# Dreamcast.net
KiCad netlist of a schematic drawn in EAGLE
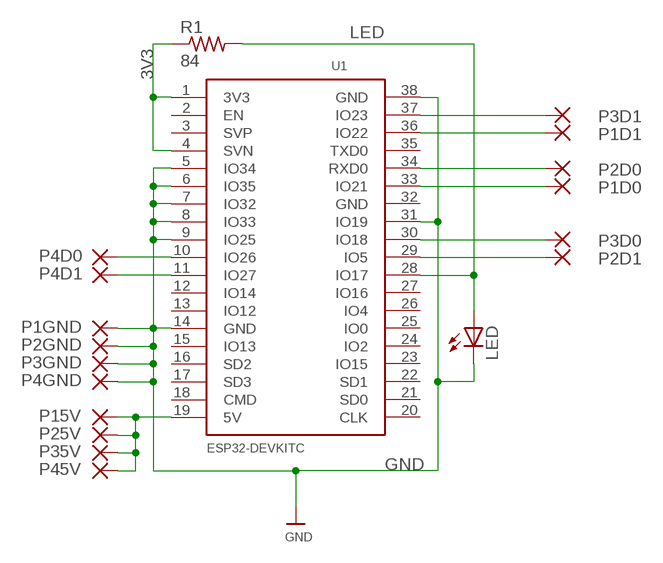
[diagram p0: schematic, sheet 1]

(export (version "E")
  (design (tool "Eeschema 10.0.6"))
  (components
    (comp (ref "LED")
      (value "LEDCHIPLED_1206")
      (footprint "eagle-import:CHIPLED_1206")
      (libsource (lib "eagle-import") (part "LEDCHIPLED_1206"))
    )
    (comp (ref "P1D0")
      (value "SMD5")
      (footprint "eagle-import:SMD2,54-5,08")
      (libsource (lib "eagle-import") (part "SMD5"))
    )
    (comp (ref "P1D1")
      (value "SMD5")
      (footprint "eagle-import:SMD2,54-5,08")
      (libsource (lib "eagle-import") (part "SMD5"))
    )
    (comp (ref "P1GND")
      (value "SMD5")
      (footprint "eagle-import:SMD2,54-5,08")
      (libsource (lib "eagle-import") (part "SMD5"))
    )
    (comp (ref "P2D0")
      (value "SMD5")
      (footprint "eagle-import:SMD2,54-5,08")
      (libsource (lib "eagle-import") (part "SMD5"))
    )
    (comp (ref "P2D1")
      (value "SMD5")
      (footprint "eagle-import:SMD2,54-5,08")
      (libsource (lib "eagle-import") (part "SMD5"))
    )
    (comp (ref "P2GND")
      (value "SMD5")
      (footprint "eagle-import:SMD2,54-5,08")
      (libsource (lib "eagle-import") (part "SMD5"))
    )
    (comp (ref "P3D0")
      (value "SMD5")
      (footprint "eagle-import:SMD2,54-5,08")
      (libsource (lib "eagle-import") (part "SMD5"))
    )
    (comp (ref "P3D1")
      (value "SMD5")
      (footprint "eagle-import:SMD2,54-5,08")
      (libsource (lib "eagle-import") (part "SMD5"))
    )
    (comp (ref "P3GND")
      (value "SMD5")
      (footprint "eagle-import:SMD2,54-5,08")
      (libsource (lib "eagle-import") (part "SMD5"))
    )
    (comp (ref "P4D0")
      (value "SMD5")
      (footprint "eagle-import:SMD2,54-5,08")
      (libsource (lib "eagle-import") (part "SMD5"))
    )
    (comp (ref "P4D1")
      (value "SMD5")
      (footprint "eagle-import:SMD2,54-5,08")
      (libsource (lib "eagle-import") (part "SMD5"))
    )
    (comp (ref "P4GND")
      (value "SMD5")
      (footprint "eagle-import:SMD2,54-5,08")
      (libsource (lib "eagle-import") (part "SMD5"))
    )
    (comp (ref "P15V")
      (value "SMD5")
      (footprint "eagle-import:SMD2,54-5,08")
      (libsource (lib "eagle-import") (part "SMD5"))
    )
    (comp (ref "P25V")
      (value "SMD5")
      (footprint "eagle-import:SMD2,54-5,08")
      (libsource (lib "eagle-import") (part "SMD5"))
    )
    (comp (ref "P35V")
      (value "SMD5")
      (footprint "eagle-import:SMD2,54-5,08")
      (libsource (lib "eagle-import") (part "SMD5"))
    )
    (comp (ref "P45V")
      (value "SMD5")
      (footprint "eagle-import:SMD2,54-5,08")
      (libsource (lib "eagle-import") (part "SMD5"))
    )
    (comp (ref "R1")
      (value "84")
      (footprint "eagle-import:R1206")
      (libsource (lib "eagle-import") (part "R-US_R1206"))
    )
    (comp (ref "U1")
      (value "ESP32DEVKITC")
      (footprint "eagle-import:ESP32-DEVKITC")
      (libsource (lib "eagle-import") (part "ESP32DEVKITC"))
    )
  )
  (nets
    (net (code "1") (name "/3V3") (class "Default")
      (node (ref "R1") (pin "1") (pinfunction "1_1") (pintype "passive"))
      (node (ref "U1") (pin "1") (pinfunction "3V3_1") (pintype "bidirectional"))
      (node (ref "U1") (pin "4") (pinfunction "SVN_4") (pintype "bidirectional"))
    )
    (net (code "2") (name "/LED") (class "Default")
      (node (ref "LED") (pin "A") (pinfunction "A_A") (pintype "passive"))
      (node (ref "R1") (pin "2") (pinfunction "2_2") (pintype "passive"))
      (node (ref "U1") (pin "28") (pinfunction "IO17_28") (pintype "bidirectional"))
    )
    (net (code "3") (name "GND") (class "Default")
      (node (ref "LED") (pin "C") (pinfunction "C_C") (pintype "passive"))
      (node (ref "P1GND") (pin "1") (pinfunction "P_1") (pintype "passive"))
      (node (ref "P2GND") (pin "1") (pinfunction "P_1") (pintype "passive"))
      (node (ref "P3GND") (pin "1") (pinfunction "P_1") (pintype "passive"))
      (node (ref "P4GND") (pin "1") (pinfunction "P_1") (pintype "passive"))
      (node (ref "U1") (pin "14") (pinfunction "GND_14") (pintype "bidirectional"))
      (node (ref "U1") (pin "31") (pinfunction "IO19_31") (pintype "bidirectional"))
      (node (ref "U1") (pin "38") (pinfunction "GND_38") (pintype "bidirectional"))
      (node (ref "U1") (pin "5") (pinfunction "IO34_5") (pintype "bidirectional"))
      (node (ref "U1") (pin "6") (pinfunction "IO35_6") (pintype "bidirectional"))
      (node (ref "U1") (pin "7") (pinfunction "IO32_7") (pintype "bidirectional"))
      (node (ref "U1") (pin "8") (pinfunction "IO33_8") (pintype "bidirectional"))
      (node (ref "U1") (pin "9") (pinfunction "IO25_9") (pintype "bidirectional"))
    )
    (net (code "4") (name "Net-(P1D0-P)") (class "Default")
      (node (ref "P1D0") (pin "1") (pinfunction "P_1") (pintype "passive"))
      (node (ref "U1") (pin "33") (pinfunction "IO21_33") (pintype "bidirectional"))
    )
    (net (code "5") (name "Net-(P1D1-P)") (class "Default")
      (node (ref "P1D1") (pin "1") (pinfunction "P_1") (pintype "passive"))
      (node (ref "U1") (pin "36") (pinfunction "IO22_36") (pintype "bidirectional"))
    )
    (net (code "6") (name "Net-(P2D0-P)") (class "Default")
      (node (ref "P2D0") (pin "1") (pinfunction "P_1") (pintype "passive"))
      (node (ref "U1") (pin "34") (pinfunction "RXD0_34") (pintype "bidirectional"))
    )
    (net (code "7") (name "Net-(P2D1-P)") (class "Default")
      (node (ref "P2D1") (pin "1") (pinfunction "P_1") (pintype "passive"))
      (node (ref "U1") (pin "29") (pinfunction "IO5_29") (pintype "bidirectional"))
    )
    (net (code "8") (name "Net-(P3D0-P)") (class "Default")
      (node (ref "P3D0") (pin "1") (pinfunction "P_1") (pintype "passive"))
      (node (ref "U1") (pin "30") (pinfunction "IO18_30") (pintype "bidirectional"))
    )
    (net (code "9") (name "Net-(P3D1-P)") (class "Default")
      (node (ref "P3D1") (pin "1") (pinfunction "P_1") (pintype "passive"))
      (node (ref "U1") (pin "37") (pinfunction "IO23_37") (pintype "bidirectional"))
    )
    (net (code "10") (name "Net-(P4D0-P)") (class "Default")
      (node (ref "P4D0") (pin "1") (pinfunction "P_1") (pintype "passive"))
      (node (ref "U1") (pin "10") (pinfunction "IO26_10") (pintype "bidirectional"))
    )
    (net (code "11") (name "Net-(P4D1-P)") (class "Default")
      (node (ref "P4D1") (pin "1") (pinfunction "P_1") (pintype "passive"))
      (node (ref "U1") (pin "11") (pinfunction "IO27_11") (pintype "bidirectional"))
    )
    (net (code "12") (name "Net-(P15V-P)") (class "Default")
      (node (ref "P15V") (pin "1") (pinfunction "P_1") (pintype "passive"))
      (node (ref "P25V") (pin "1") (pinfunction "P_1") (pintype "passive"))
      (node (ref "P35V") (pin "1") (pinfunction "P_1") (pintype "passive"))
      (node (ref "P45V") (pin "1") (pinfunction "P_1") (pintype "passive"))
      (node (ref "U1") (pin "19") (pinfunction "5V_19") (pintype "bidirectional"))
    )
    (net (code "13") (name "unconnected-(U1-CLK-Pad20)") (class "Default")
      (node (ref "U1") (pin "20") (pinfunction "CLK_20") (pintype "bidirectional"))
    )
    (net (code "14") (name "unconnected-(U1-CMD-Pad18)") (class "Default")
      (node (ref "U1") (pin "18") (pinfunction "CMD_18") (pintype "bidirectional"))
    )
    (net (code "15") (name "unconnected-(U1-EN-Pad2)") (class "Default")
      (node (ref "U1") (pin "2") (pinfunction "EN_2") (pintype "bidirectional"))
    )
    (net (code "16") (name "unconnected-(U1-GND-Pad32)") (class "Default")
      (node (ref "U1") (pin "32") (pinfunction "GND_32") (pintype "bidirectional"))
    )
    (net (code "17") (name "unconnected-(U1-IO0-Pad25)") (class "Default")
      (node (ref "U1") (pin "25") (pinfunction "IO0_25") (pintype "bidirectional"))
    )
    (net (code "18") (name "unconnected-(U1-IO2-Pad24)") (class "Default")
      (node (ref "U1") (pin "24") (pinfunction "IO2_24") (pintype "bidirectional"))
    )
    (net (code "19") (name "unconnected-(U1-IO4-Pad26)") (class "Default")
      (node (ref "U1") (pin "26") (pinfunction "IO4_26") (pintype "bidirectional"))
    )
    (net (code "20") (name "unconnected-(U1-IO12-Pad13)") (class "Default")
      (node (ref "U1") (pin "13") (pinfunction "IO12_13") (pintype "bidirectional"))
    )
    (net (code "21") (name "unconnected-(U1-IO13-Pad15)") (class "Default")
      (node (ref "U1") (pin "15") (pinfunction "IO13_15") (pintype "bidirectional"))
    )
    (net (code "22") (name "unconnected-(U1-IO14-Pad12)") (class "Default")
      (node (ref "U1") (pin "12") (pinfunction "IO14_12") (pintype "bidirectional"))
    )
    (net (code "23") (name "unconnected-(U1-IO15-Pad23)") (class "Default")
      (node (ref "U1") (pin "23") (pinfunction "IO15_23") (pintype "bidirectional"))
    )
    (net (code "24") (name "unconnected-(U1-IO16-Pad27)") (class "Default")
      (node (ref "U1") (pin "27") (pinfunction "IO16_27") (pintype "bidirectional"))
    )
    (net (code "25") (name "unconnected-(U1-SD0-Pad21)") (class "Default")
      (node (ref "U1") (pin "21") (pinfunction "SD0_21") (pintype "bidirectional"))
    )
    (net (code "26") (name "unconnected-(U1-SD1-Pad22)") (class "Default")
      (node (ref "U1") (pin "22") (pinfunction "SD1_22") (pintype "bidirectional"))
    )
    (net (code "27") (name "unconnected-(U1-SD2-Pad16)") (class "Default")
      (node (ref "U1") (pin "16") (pinfunction "SD2_16") (pintype "bidirectional"))
    )
    (net (code "28") (name "unconnected-(U1-SD3-Pad17)") (class "Default")
      (node (ref "U1") (pin "17") (pinfunction "SD3_17") (pintype "bidirectional"))
    )
    (net (code "29") (name "unconnected-(U1-SVP-Pad3)") (class "Default")
      (node (ref "U1") (pin "3") (pinfunction "SVP_3") (pintype "bidirectional"))
    )
    (net (code "30") (name "unconnected-(U1-TXD0-Pad35)") (class "Default")
      (node (ref "U1") (pin "35") (pinfunction "TXD0_35") (pintype "bidirectional"))
    )
  )
)
